# isa_cvx.net
KiCad netlist of a schematic drawn in EAGLE
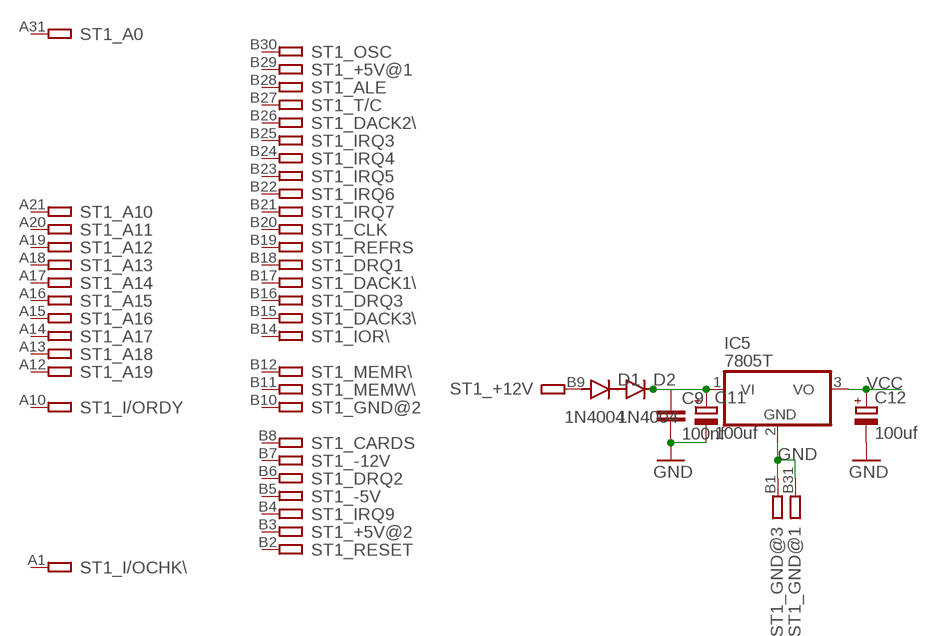
[diagram p0: schematic, sheet 1, part 1 of 2]
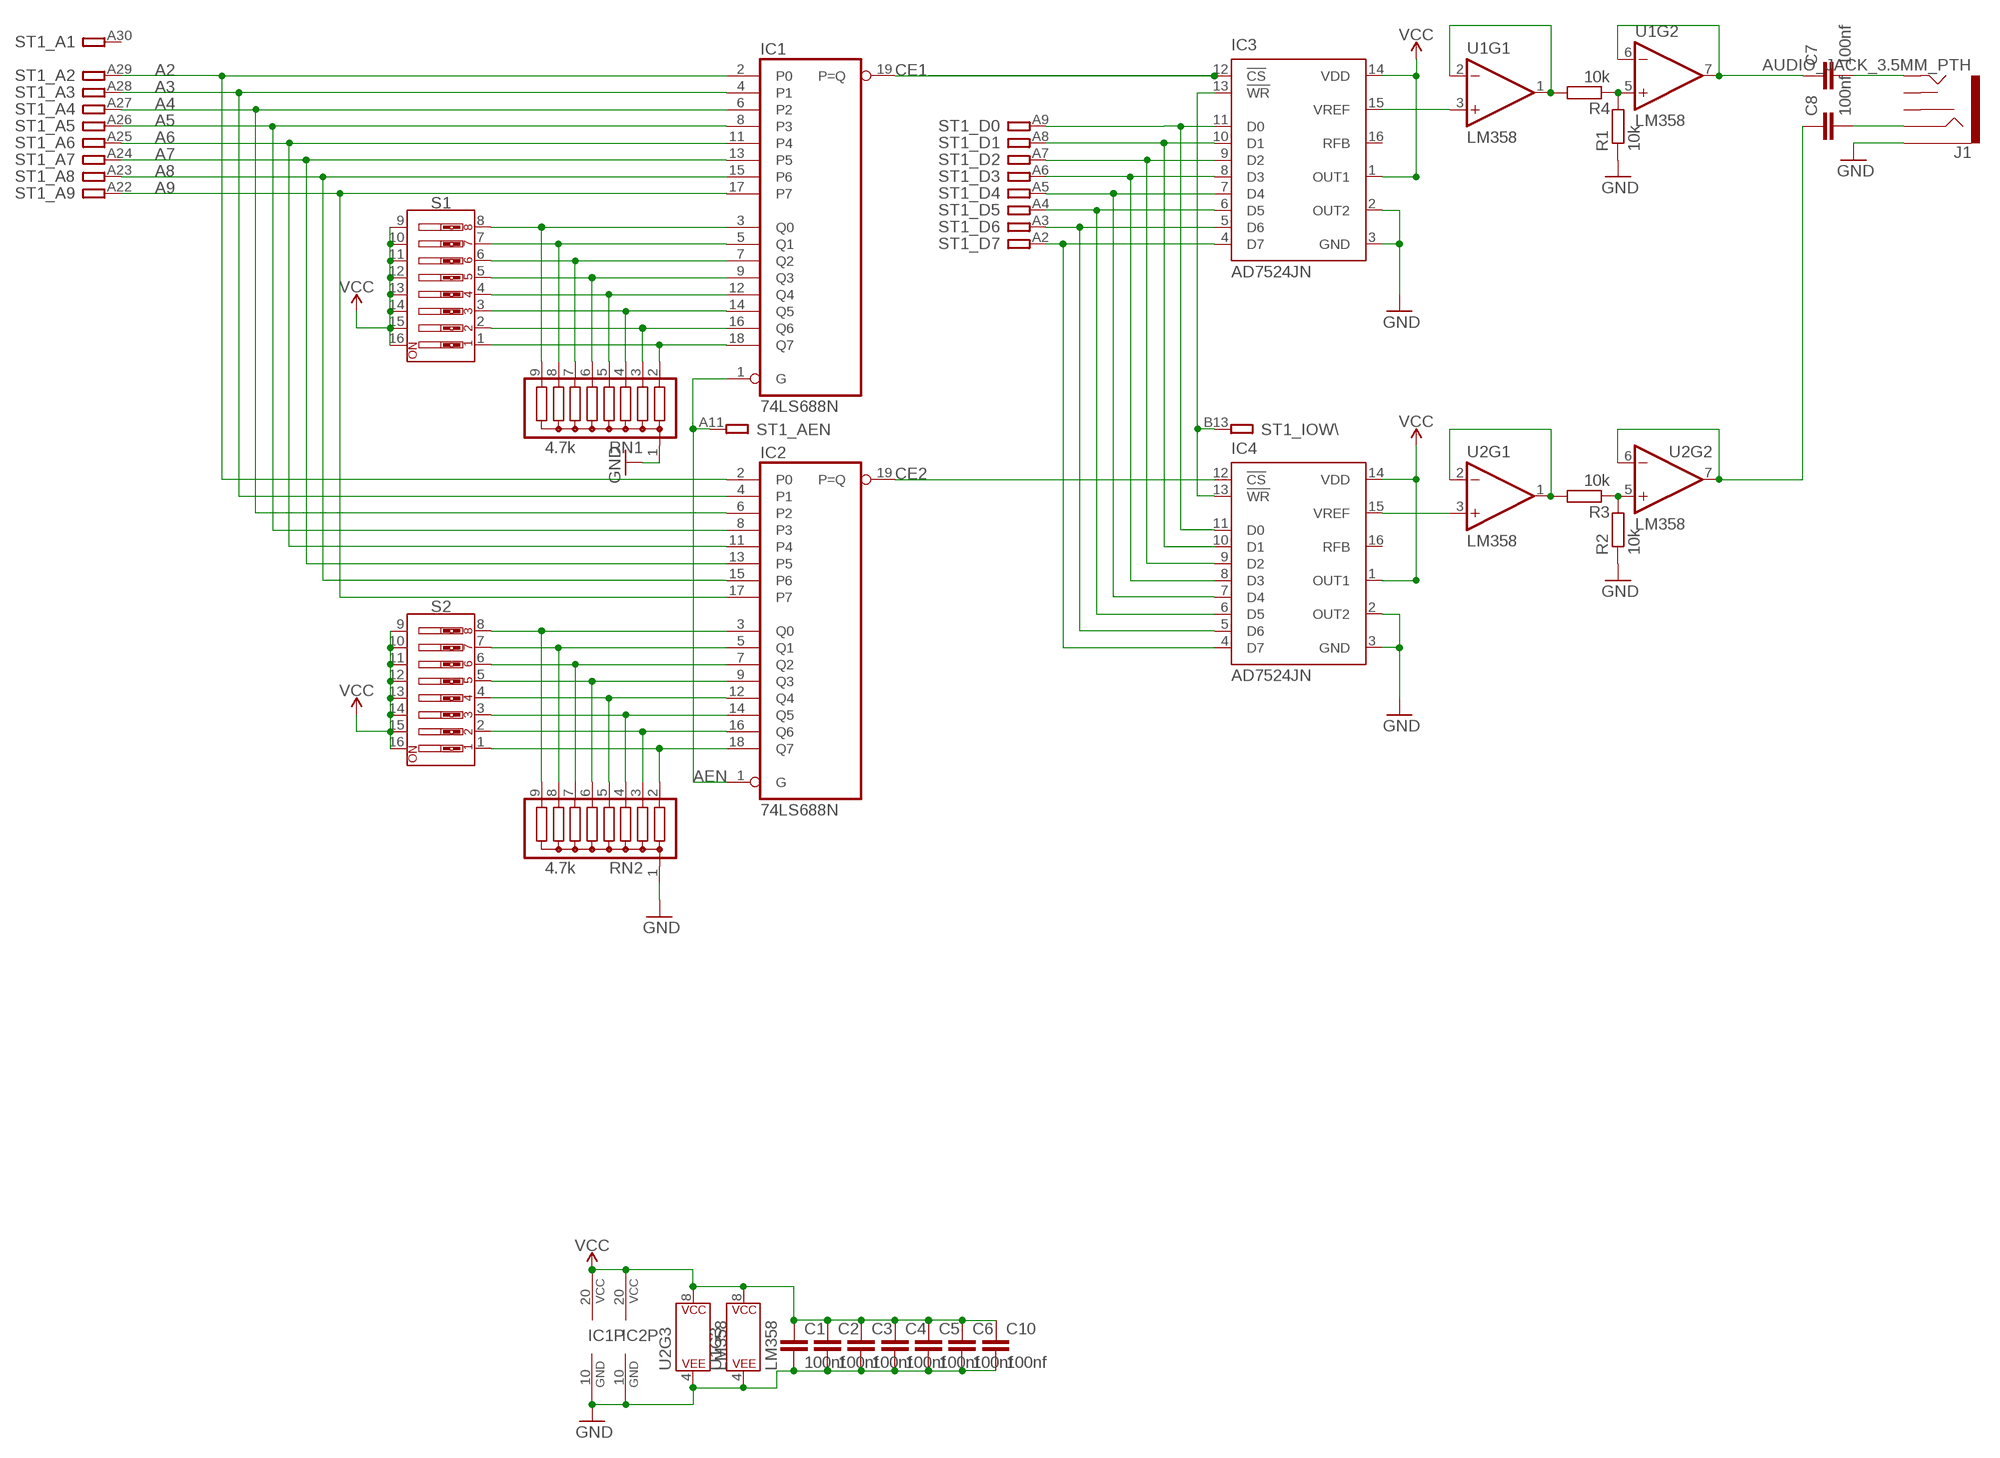
[diagram p1: schematic, sheet 1, part 2 of 2]

(export (version "E")
  (design (tool "Eeschema 10.0.6"))
  (components
    (comp (ref "C1")
      (value "100nf")
      (footprint "eagle-import:C2.5-2")
      (libsource (lib "eagle-import") (part "C2.5/2"))
    )
    (comp (ref "C2")
      (value "100nf")
      (footprint "eagle-import:C2.5-2")
      (libsource (lib "eagle-import") (part "C2.5/2"))
    )
    (comp (ref "C3")
      (value "100nf")
      (footprint "eagle-import:C2.5-2")
      (libsource (lib "eagle-import") (part "C2.5/2"))
    )
    (comp (ref "C4")
      (value "100nf")
      (footprint "eagle-import:C2.5-2")
      (libsource (lib "eagle-import") (part "C2.5/2"))
    )
    (comp (ref "C5")
      (value "100nf")
      (footprint "eagle-import:C2.5-2")
      (libsource (lib "eagle-import") (part "C2.5/2"))
    )
    (comp (ref "C6")
      (value "100nf")
      (footprint "eagle-import:C2.5-2")
      (libsource (lib "eagle-import") (part "C2.5/2"))
    )
    (comp (ref "C7")
      (value "100nf")
      (footprint "eagle-import:C2.5-2")
      (libsource (lib "eagle-import") (part "C2.5/2"))
    )
    (comp (ref "C8")
      (value "100nf")
      (footprint "eagle-import:C2.5-2")
      (libsource (lib "eagle-import") (part "C2.5/2"))
    )
    (comp (ref "C9")
      (value "100nf")
      (footprint "eagle-import:C2.5-2")
      (libsource (lib "eagle-import") (part "C2.5/2"))
    )
    (comp (ref "C10")
      (value "100nf")
      (footprint "eagle-import:C2.5-2")
      (libsource (lib "eagle-import") (part "C2.5/2"))
    )
    (comp (ref "C11")
      (value "100uf")
      (footprint "eagle-import:E2,5-5")
      (libsource (lib "eagle-import") (part "CPOL-EUE2.5-5"))
    )
    (comp (ref "C12")
      (value "100uf")
      (footprint "eagle-import:E2,5-5")
      (libsource (lib "eagle-import") (part "CPOL-EUE2.5-5"))
    )
    (comp (ref "D1")
      (value "1N4004")
      (footprint "eagle-import:DO41-10")
      (libsource (lib "eagle-import") (part "1N4004"))
    )
    (comp (ref "D2")
      (value "1N4004")
      (footprint "eagle-import:DO41-10")
      (libsource (lib "eagle-import") (part "1N4004"))
    )
    (comp (ref "IC1")
      (value "74LS688N")
      (footprint "eagle-import:DIL20")
      (libsource (lib "eagle-import") (part "74688NLS"))
    )
    (comp (ref "IC2")
      (value "74LS688N")
      (footprint "eagle-import:DIL20")
      (libsource (lib "eagle-import") (part "74688NLS"))
    )
    (comp (ref "IC3")
      (value "AD7524JN")
      (footprint "eagle-import:DIL16")
      (fields (field (name "MF") "ALTERA CORPORATION") (field (name "MPN") "AD7524JNZ"))
      (libsource (lib "eagle-import") (part "AD7524NJ"))
    )
    (comp (ref "IC4")
      (value "AD7524JN")
      (footprint "eagle-import:DIL16")
      (fields (field (name "MF") "ALTERA CORPORATION") (field (name "MPN") "AD7524JNZ"))
      (libsource (lib "eagle-import") (part "AD7524NJ"))
    )
    (comp (ref "IC5")
      (value "7805T")
      (footprint "eagle-import:TO220H")
      (libsource (lib "eagle-import") (part "78T05"))
    )
    (comp (ref "J1")
      (value "AUDIO_JACK_3.5MM_PTH")
      (footprint "eagle-import:AUDIO-JACK")
      (libsource (lib "eagle-import") (part "AUDIO_JACK_3.5MM_PTH"))
    )
    (comp (ref "R1")
      (value "10k")
      (footprint "eagle-import:0207_10")
      (libsource (lib "eagle-import") (part "R-EU_0207/10"))
    )
    (comp (ref "R2")
      (value "10k")
      (footprint "eagle-import:0207_10")
      (libsource (lib "eagle-import") (part "R-EU_0207/10"))
    )
    (comp (ref "R3")
      (value "10k")
      (footprint "eagle-import:0207_10")
      (libsource (lib "eagle-import") (part "R-EU_0207/10"))
    )
    (comp (ref "R4")
      (value "10k")
      (footprint "eagle-import:0207_10")
      (libsource (lib "eagle-import") (part "R-EU_0207/10"))
    )
    (comp (ref "RN1")
      (value "4.7k")
      (footprint "eagle-import:SIL9")
      (libsource (lib "eagle-import") (part "G08R"))
    )
    (comp (ref "RN2")
      (value "4.7k")
      (footprint "eagle-import:SIL9")
      (libsource (lib "eagle-import") (part "G08R"))
    )
    (comp (ref "S1")
      (value "DIP-08-PTH")
      (footprint "eagle-import:DIPSWITCH-08")
      (libsource (lib "eagle-import") (part "DIP-08-PTH"))
    )
    (comp (ref "S2")
      (value "DIP-08-PTH")
      (footprint "eagle-import:DIPSWITCH-08")
      (libsource (lib "eagle-import") (part "DIP-08-PTH"))
    )
    (comp (ref "ST1")
      (value "IBM8BIT")
      (footprint "eagle-import:IBM8BIT")
      (libsource (lib "eagle-import") (part "IBM8BIT"))
    )
    (comp (ref "U1")
      (value "LM358")
      (footprint "eagle-import:DIP08")
      (libsource (lib "eagle-import") (part "LM358"))
    )
    (comp (ref "U2")
      (value "LM358")
      (footprint "eagle-import:DIP08")
      (libsource (lib "eagle-import") (part "LM358"))
    )
  )
  (nets
    (net (code "1") (name "/A2") (class "Default")
      (node (ref "IC1") (pin "2") (pinfunction "P0_2") (pintype "input"))
      (node (ref "IC2") (pin "2") (pinfunction "P0_2") (pintype "input"))
      (node (ref "ST1") (pin "A29") (pinfunction "P_A29") (pintype "bidirectional"))
    )
    (net (code "2") (name "/A3") (class "Default")
      (node (ref "IC1") (pin "4") (pinfunction "P1_4") (pintype "input"))
      (node (ref "IC2") (pin "4") (pinfunction "P1_4") (pintype "input"))
      (node (ref "ST1") (pin "A28") (pinfunction "P_A28") (pintype "bidirectional"))
    )
    (net (code "3") (name "/A4") (class "Default")
      (node (ref "IC1") (pin "6") (pinfunction "P2_6") (pintype "input"))
      (node (ref "IC2") (pin "6") (pinfunction "P2_6") (pintype "input"))
      (node (ref "ST1") (pin "A27") (pinfunction "P_A27") (pintype "bidirectional"))
    )
    (net (code "4") (name "/A5") (class "Default")
      (node (ref "IC1") (pin "8") (pinfunction "P3_8") (pintype "input"))
      (node (ref "IC2") (pin "8") (pinfunction "P3_8") (pintype "input"))
      (node (ref "ST1") (pin "A26") (pinfunction "P_A26") (pintype "bidirectional"))
    )
    (net (code "5") (name "/A6") (class "Default")
      (node (ref "IC1") (pin "11") (pinfunction "P4_11") (pintype "input"))
      (node (ref "IC2") (pin "11") (pinfunction "P4_11") (pintype "input"))
      (node (ref "ST1") (pin "A25") (pinfunction "P_A25") (pintype "bidirectional"))
    )
    (net (code "6") (name "/A7") (class "Default")
      (node (ref "IC1") (pin "13") (pinfunction "P5_13") (pintype "input"))
      (node (ref "IC2") (pin "13") (pinfunction "P5_13") (pintype "input"))
      (node (ref "ST1") (pin "A24") (pinfunction "P_A24") (pintype "bidirectional"))
    )
    (net (code "7") (name "/A8") (class "Default")
      (node (ref "IC1") (pin "15") (pinfunction "P6_15") (pintype "input"))
      (node (ref "IC2") (pin "15") (pinfunction "P6_15") (pintype "input"))
      (node (ref "ST1") (pin "A23") (pinfunction "P_A23") (pintype "bidirectional"))
    )
    (net (code "8") (name "/A9") (class "Default")
      (node (ref "IC1") (pin "17") (pinfunction "P7_17") (pintype "input"))
      (node (ref "IC2") (pin "17") (pinfunction "P7_17") (pintype "input"))
      (node (ref "ST1") (pin "A22") (pinfunction "P_A22") (pintype "bidirectional"))
    )
    (net (code "9") (name "/AEN") (class "Default")
      (node (ref "IC1") (pin "1") (pinfunction "G_1") (pintype "input"))
      (node (ref "IC2") (pin "1") (pinfunction "G_1") (pintype "input"))
      (node (ref "ST1") (pin "A11") (pinfunction "P_A11") (pintype "bidirectional"))
    )
    (net (code "10") (name "/CE1") (class "Default")
      (node (ref "IC1") (pin "19") (pinfunction "P=Q_19") (pintype "output"))
      (node (ref "IC3") (pin "12") (pinfunction "~{CS}_12") (pintype "input"))
    )
    (net (code "11") (name "/CE2") (class "Default")
      (node (ref "IC2") (pin "19") (pinfunction "P=Q_19") (pintype "output"))
      (node (ref "IC4") (pin "12") (pinfunction "~{CS}_12") (pintype "input"))
    )
    (net (code "12") (name "GND") (class "Default")
      (node (ref "C1") (pin "2") (pinfunction "2_2") (pintype "passive"))
      (node (ref "C10") (pin "2") (pinfunction "2_2") (pintype "passive"))
      (node (ref "C11") (pin "-") (pinfunction "-_-") (pintype "passive"))
      (node (ref "C12") (pin "-") (pinfunction "-_-") (pintype "passive"))
      (node (ref "C2") (pin "2") (pinfunction "2_2") (pintype "passive"))
      (node (ref "C3") (pin "2") (pinfunction "2_2") (pintype "passive"))
      (node (ref "C4") (pin "2") (pinfunction "2_2") (pintype "passive"))
      (node (ref "C5") (pin "2") (pinfunction "2_2") (pintype "passive"))
      (node (ref "C6") (pin "2") (pinfunction "2_2") (pintype "passive"))
      (node (ref "C9") (pin "2") (pinfunction "2_2") (pintype "passive"))
      (node (ref "IC1") (pin "10") (pinfunction "GND_10") (pintype "power_in"))
      (node (ref "IC2") (pin "10") (pinfunction "GND_10") (pintype "power_in"))
      (node (ref "IC3") (pin "2") (pinfunction "OUT2_2") (pintype "passive"))
      (node (ref "IC3") (pin "3") (pinfunction "GND_3") (pintype "power_in"))
      (node (ref "IC4") (pin "2") (pinfunction "OUT2_2") (pintype "passive"))
      (node (ref "IC4") (pin "3") (pinfunction "GND_3") (pintype "power_in"))
      (node (ref "IC5") (pin "2") (pinfunction "GND_2") (pintype "passive"))
      (node (ref "J1") (pin "SLEEVE") (pinfunction "SLEEVE_SLEEVE") (pintype "bidirectional"))
      (node (ref "R1") (pin "1") (pinfunction "1_1") (pintype "passive"))
      (node (ref "R2") (pin "1") (pinfunction "1_1") (pintype "passive"))
      (node (ref "RN1") (pin "1") (pinfunction "1_1") (pintype "passive"))
      (node (ref "RN2") (pin "1") (pinfunction "1_1") (pintype "passive"))
      (node (ref "ST1") (pin "B1") (pinfunction "P_B1") (pintype "bidirectional"))
      (node (ref "ST1") (pin "B31") (pinfunction "P_B31") (pintype "bidirectional"))
      (node (ref "U1") (pin "4") (pinfunction "P$V-_4") (pintype "bidirectional"))
      (node (ref "U2") (pin "4") (pinfunction "P$V-_4") (pintype "bidirectional"))
    )
    (net (code "13") (name "Net-(C7-Pad2)") (class "Default")
      (node (ref "C7") (pin "2") (pinfunction "2_2") (pintype "passive"))
      (node (ref "J1") (pin "TIP") (pinfunction "TIP_TIP") (pintype "bidirectional"))
    )
    (net (code "14") (name "Net-(C8-Pad2)") (class "Default")
      (node (ref "C8") (pin "2") (pinfunction "2_2") (pintype "passive"))
      (node (ref "J1") (pin "RING") (pinfunction "RING_RING") (pintype "bidirectional"))
    )
    (net (code "15") (name "Net-(D1-PadC)") (class "Default")
      (node (ref "D1") (pin "C") (pinfunction "C_C") (pintype "passive"))
      (node (ref "D2") (pin "A") (pinfunction "A_A") (pintype "passive"))
    )
    (net (code "16") (name "Net-(IC1A-Q0)") (class "Default")
      (node (ref "IC1") (pin "3") (pinfunction "Q0_3") (pintype "input"))
      (node (ref "RN1") (pin "9") (pinfunction "9_9") (pintype "passive"))
      (node (ref "S1") (pin "8") (pinfunction "8_8") (pintype "passive"))
    )
    (net (code "17") (name "Net-(IC1A-Q1)") (class "Default")
      (node (ref "IC1") (pin "5") (pinfunction "Q1_5") (pintype "input"))
      (node (ref "RN1") (pin "8") (pinfunction "8_8") (pintype "passive"))
      (node (ref "S1") (pin "7") (pinfunction "7_7") (pintype "passive"))
    )
    (net (code "18") (name "Net-(IC1A-Q2)") (class "Default")
      (node (ref "IC1") (pin "7") (pinfunction "Q2_7") (pintype "input"))
      (node (ref "RN1") (pin "7") (pinfunction "7_7") (pintype "passive"))
      (node (ref "S1") (pin "6") (pinfunction "6_6") (pintype "passive"))
    )
    (net (code "19") (name "Net-(IC1A-Q3)") (class "Default")
      (node (ref "IC1") (pin "9") (pinfunction "Q3_9") (pintype "input"))
      (node (ref "RN1") (pin "6") (pinfunction "6_6") (pintype "passive"))
      (node (ref "S1") (pin "5") (pinfunction "5_5") (pintype "passive"))
    )
    (net (code "20") (name "Net-(IC1A-Q4)") (class "Default")
      (node (ref "IC1") (pin "12") (pinfunction "Q4_12") (pintype "input"))
      (node (ref "RN1") (pin "5") (pinfunction "5_5") (pintype "passive"))
      (node (ref "S1") (pin "4") (pinfunction "4_4") (pintype "passive"))
    )
    (net (code "21") (name "Net-(IC1A-Q5)") (class "Default")
      (node (ref "IC1") (pin "14") (pinfunction "Q5_14") (pintype "input"))
      (node (ref "RN1") (pin "4") (pinfunction "4_4") (pintype "passive"))
      (node (ref "S1") (pin "3") (pinfunction "3_3") (pintype "passive"))
    )
    (net (code "22") (name "Net-(IC1A-Q6)") (class "Default")
      (node (ref "IC1") (pin "16") (pinfunction "Q6_16") (pintype "input"))
      (node (ref "RN1") (pin "3") (pinfunction "3_3") (pintype "passive"))
      (node (ref "S1") (pin "2") (pinfunction "2_2") (pintype "passive"))
    )
    (net (code "23") (name "Net-(IC1A-Q7)") (class "Default")
      (node (ref "IC1") (pin "18") (pinfunction "Q7_18") (pintype "input"))
      (node (ref "RN1") (pin "2") (pinfunction "2_2") (pintype "passive"))
      (node (ref "S1") (pin "1") (pinfunction "1_1") (pintype "passive"))
    )
    (net (code "24") (name "Net-(IC2A-Q0)") (class "Default")
      (node (ref "IC2") (pin "3") (pinfunction "Q0_3") (pintype "input"))
      (node (ref "RN2") (pin "9") (pinfunction "9_9") (pintype "passive"))
      (node (ref "S2") (pin "8") (pinfunction "8_8") (pintype "passive"))
    )
    (net (code "25") (name "Net-(IC2A-Q1)") (class "Default")
      (node (ref "IC2") (pin "5") (pinfunction "Q1_5") (pintype "input"))
      (node (ref "RN2") (pin "8") (pinfunction "8_8") (pintype "passive"))
      (node (ref "S2") (pin "7") (pinfunction "7_7") (pintype "passive"))
    )
    (net (code "26") (name "Net-(IC2A-Q2)") (class "Default")
      (node (ref "IC2") (pin "7") (pinfunction "Q2_7") (pintype "input"))
      (node (ref "RN2") (pin "7") (pinfunction "7_7") (pintype "passive"))
      (node (ref "S2") (pin "6") (pinfunction "6_6") (pintype "passive"))
    )
    (net (code "27") (name "Net-(IC2A-Q3)") (class "Default")
      (node (ref "IC2") (pin "9") (pinfunction "Q3_9") (pintype "input"))
      (node (ref "RN2") (pin "6") (pinfunction "6_6") (pintype "passive"))
      (node (ref "S2") (pin "5") (pinfunction "5_5") (pintype "passive"))
    )
    (net (code "28") (name "Net-(IC2A-Q4)") (class "Default")
      (node (ref "IC2") (pin "12") (pinfunction "Q4_12") (pintype "input"))
      (node (ref "RN2") (pin "5") (pinfunction "5_5") (pintype "passive"))
      (node (ref "S2") (pin "4") (pinfunction "4_4") (pintype "passive"))
    )
    (net (code "29") (name "Net-(IC2A-Q5)") (class "Default")
      (node (ref "IC2") (pin "14") (pinfunction "Q5_14") (pintype "input"))
      (node (ref "RN2") (pin "4") (pinfunction "4_4") (pintype "passive"))
      (node (ref "S2") (pin "3") (pinfunction "3_3") (pintype "passive"))
    )
    (net (code "30") (name "Net-(IC2A-Q6)") (class "Default")
      (node (ref "IC2") (pin "16") (pinfunction "Q6_16") (pintype "input"))
      (node (ref "RN2") (pin "3") (pinfunction "3_3") (pintype "passive"))
      (node (ref "S2") (pin "2") (pinfunction "2_2") (pintype "passive"))
    )
    (net (code "31") (name "Net-(IC2A-Q7)") (class "Default")
      (node (ref "IC2") (pin "18") (pinfunction "Q7_18") (pintype "input"))
      (node (ref "RN2") (pin "2") (pinfunction "2_2") (pintype "passive"))
      (node (ref "S2") (pin "1") (pinfunction "1_1") (pintype "passive"))
    )
    (net (code "32") (name "Net-(IC3-D0)") (class "Default")
      (node (ref "IC3") (pin "11") (pinfunction "D0_11") (pintype "input"))
      (node (ref "IC4") (pin "11") (pinfunction "D0_11") (pintype "input"))
      (node (ref "ST1") (pin "A9") (pinfunction "P_A9") (pintype "bidirectional"))
    )
    (net (code "33") (name "Net-(IC3-D1)") (class "Default")
      (node (ref "IC3") (pin "10") (pinfunction "D1_10") (pintype "input"))
      (node (ref "IC4") (pin "10") (pinfunction "D1_10") (pintype "input"))
      (node (ref "ST1") (pin "A8") (pinfunction "P_A8") (pintype "bidirectional"))
    )
    (net (code "34") (name "Net-(IC3-D2)") (class "Default")
      (node (ref "IC3") (pin "9") (pinfunction "D2_9") (pintype "input"))
      (node (ref "IC4") (pin "9") (pinfunction "D2_9") (pintype "input"))
      (node (ref "ST1") (pin "A7") (pinfunction "P_A7") (pintype "bidirectional"))
    )
    (net (code "35") (name "Net-(IC3-D3)") (class "Default")
      (node (ref "IC3") (pin "8") (pinfunction "D3_8") (pintype "input"))
      (node (ref "IC4") (pin "8") (pinfunction "D3_8") (pintype "input"))
      (node (ref "ST1") (pin "A6") (pinfunction "P_A6") (pintype "bidirectional"))
    )
    (net (code "36") (name "Net-(IC3-D4)") (class "Default")
      (node (ref "IC3") (pin "7") (pinfunction "D4_7") (pintype "input"))
      (node (ref "IC4") (pin "7") (pinfunction "D4_7") (pintype "input"))
      (node (ref "ST1") (pin "A5") (pinfunction "P_A5") (pintype "bidirectional"))
    )
    (net (code "37") (name "Net-(IC3-D5)") (class "Default")
      (node (ref "IC3") (pin "6") (pinfunction "D5_6") (pintype "input"))
      (node (ref "IC4") (pin "6") (pinfunction "D5_6") (pintype "input"))
      (node (ref "ST1") (pin "A4") (pinfunction "P_A4") (pintype "bidirectional"))
    )
    (net (code "38") (name "Net-(IC3-D6)") (class "Default")
      (node (ref "IC3") (pin "5") (pinfunction "D6_5") (pintype "input"))
      (node (ref "IC4") (pin "5") (pinfunction "D6_5") (pintype "input"))
      (node (ref "ST1") (pin "A3") (pinfunction "P_A3") (pintype "bidirectional"))
    )
    (net (code "39") (name "Net-(IC3-D7)") (class "Default")
      (node (ref "IC3") (pin "4") (pinfunction "D7_4") (pintype "input"))
      (node (ref "IC4") (pin "4") (pinfunction "D7_4") (pintype "input"))
      (node (ref "ST1") (pin "A2") (pinfunction "P_A2") (pintype "bidirectional"))
    )
    (net (code "40") (name "Net-(IC3-VREF)") (class "Default")
      (node (ref "IC3") (pin "15") (pinfunction "VREF_15") (pintype "input"))
      (node (ref "U1") (pin "3") (pinfunction "+IN_3") (pintype "input"))
    )
    (net (code "41") (name "Net-(IC3-~{WR})") (class "Default")
      (node (ref "IC3") (pin "13") (pinfunction "~{WR}_13") (pintype "input"))
      (node (ref "IC4") (pin "13") (pinfunction "~{WR}_13") (pintype "input"))
      (node (ref "ST1") (pin "B13") (pinfunction "P_B13") (pintype "bidirectional"))
    )
    (net (code "42") (name "Net-(IC4-VREF)") (class "Default")
      (node (ref "IC4") (pin "15") (pinfunction "VREF_15") (pintype "input"))
      (node (ref "U2") (pin "3") (pinfunction "+IN_3") (pintype "input"))
    )
    (net (code "43") (name "Net-(IC5-VI)") (class "Default")
      (node (ref "C11") (pin "+") (pinfunction "+_+") (pintype "passive"))
      (node (ref "C9") (pin "1") (pinfunction "1_1") (pintype "passive"))
      (node (ref "D2") (pin "C") (pinfunction "C_C") (pintype "passive"))
      (node (ref "IC5") (pin "1") (pinfunction "VI_1") (pintype "input"))
    )
    (net (code "44") (name "Net-(ST1A-P)") (class "Default")
      (node (ref "D1") (pin "A") (pinfunction "A_A") (pintype "passive"))
      (node (ref "ST1") (pin "B9") (pinfunction "P_B9") (pintype "bidirectional"))
    )
    (net (code "45") (name "Net-(U1A--IN)") (class "Default")
      (node (ref "R4") (pin "2") (pinfunction "2_2") (pintype "passive"))
      (node (ref "U1") (pin "1") (pinfunction "OUT_1") (pintype "output"))
      (node (ref "U1") (pin "2") (pinfunction "-IN_2") (pintype "input"))
    )
    (net (code "46") (name "Net-(U1B-+IN)") (class "Default")
      (node (ref "R1") (pin "2") (pinfunction "2_2") (pintype "passive"))
      (node (ref "R4") (pin "1") (pinfunction "1_1") (pintype "passive"))
      (node (ref "U1") (pin "5") (pinfunction "+IN_5") (pintype "input"))
    )
    (net (code "47") (name "Net-(U1B--IN)") (class "Default")
      (node (ref "C7") (pin "1") (pinfunction "1_1") (pintype "passive"))
      (node (ref "U1") (pin "6") (pinfunction "-IN_6") (pintype "input"))
      (node (ref "U1") (pin "7") (pinfunction "OUT_7") (pintype "output"))
    )
    (net (code "48") (name "Net-(U2A--IN)") (class "Default")
      (node (ref "R3") (pin "2") (pinfunction "2_2") (pintype "passive"))
      (node (ref "U2") (pin "1") (pinfunction "OUT_1") (pintype "output"))
      (node (ref "U2") (pin "2") (pinfunction "-IN_2") (pintype "input"))
    )
    (net (code "49") (name "Net-(U2B-+IN)") (class "Default")
      (node (ref "R2") (pin "2") (pinfunction "2_2") (pintype "passive"))
      (node (ref "R3") (pin "1") (pinfunction "1_1") (pintype "passive"))
      (node (ref "U2") (pin "5") (pinfunction "+IN_5") (pintype "input"))
    )
    (net (code "50") (name "Net-(U2B--IN)") (class "Default")
      (node (ref "C8") (pin "1") (pinfunction "1_1") (pintype "passive"))
      (node (ref "U2") (pin "6") (pinfunction "-IN_6") (pintype "input"))
      (node (ref "U2") (pin "7") (pinfunction "OUT_7") (pintype "output"))
    )
    (net (code "51") (name "VCC") (class "Default")
      (node (ref "C1") (pin "1") (pinfunction "1_1") (pintype "passive"))
      (node (ref "C10") (pin "1") (pinfunction "1_1") (pintype "passive"))
      (node (ref "C12") (pin "+") (pinfunction "+_+") (pintype "passive"))
      (node (ref "C2") (pin "1") (pinfunction "1_1") (pintype "passive"))
      (node (ref "C3") (pin "1") (pinfunction "1_1") (pintype "passive"))
      (node (ref "C4") (pin "1") (pinfunction "1_1") (pintype "passive"))
      (node (ref "C5") (pin "1") (pinfunction "1_1") (pintype "passive"))
      (node (ref "C6") (pin "1") (pinfunction "1_1") (pintype "passive"))
      (node (ref "IC1") (pin "20") (pinfunction "VCC_20") (pintype "power_in"))
      (node (ref "IC2") (pin "20") (pinfunction "VCC_20") (pintype "power_in"))
      (node (ref "IC3") (pin "1") (pinfunction "OUT1_1") (pintype "passive"))
      (node (ref "IC3") (pin "14") (pinfunction "VDD_14") (pintype "power_in"))
      (node (ref "IC4") (pin "1") (pinfunction "OUT1_1") (pintype "passive"))
      (node (ref "IC4") (pin "14") (pinfunction "VDD_14") (pintype "power_in"))
      (node (ref "IC5") (pin "3") (pinfunction "VO_3") (pintype "passive"))
      (node (ref "S1") (pin "10") (pinfunction "10_10") (pintype "passive"))
      (node (ref "S1") (pin "11") (pinfunction "11_11") (pintype "passive"))
      (node (ref "S1") (pin "12") (pinfunction "12_12") (pintype "passive"))
      (node (ref "S1") (pin "13") (pinfunction "13_13") (pintype "passive"))
      (node (ref "S1") (pin "14") (pinfunction "14_14") (pintype "passive"))
      (node (ref "S1") (pin "15") (pinfunction "15_15") (pintype "passive"))
      (node (ref "S1") (pin "16") (pinfunction "16_16") (pintype "passive"))
      (node (ref "S1") (pin "9") (pinfunction "9_9") (pintype "passive"))
      (node (ref "S2") (pin "10") (pinfunction "10_10") (pintype "passive"))
      (node (ref "S2") (pin "11") (pinfunction "11_11") (pintype "passive"))
      (node (ref "S2") (pin "12") (pinfunction "12_12") (pintype "passive"))
      (node (ref "S2") (pin "13") (pinfunction "13_13") (pintype "passive"))
      (node (ref "S2") (pin "14") (pinfunction "14_14") (pintype "passive"))
      (node (ref "S2") (pin "15") (pinfunction "15_15") (pintype "passive"))
      (node (ref "S2") (pin "16") (pinfunction "16_16") (pintype "passive"))
      (node (ref "S2") (pin "9") (pinfunction "9_9") (pintype "passive"))
      (node (ref "U1") (pin "8") (pinfunction "P$V+_8") (pintype "bidirectional"))
      (node (ref "U2") (pin "8") (pinfunction "P$V+_8") (pintype "bidirectional"))
    )
    (net (code "52") (name "unconnected-(IC3-RFB-Pad16)") (class "Default")
      (node (ref "IC3") (pin "16") (pinfunction "RFB_16") (pintype "passive"))
    )
    (net (code "53") (name "unconnected-(IC4-RFB-Pad16)") (class "Default")
      (node (ref "IC4") (pin "16") (pinfunction "RFB_16") (pintype "passive"))
    )
    (net (code "54") (name "unconnected-(J1-PadRSH)") (class "Default")
      (node (ref "J1") (pin "RSH") (pinfunction "RSH_RSH") (pintype "bidirectional"))
    )
    (net (code "55") (name "unconnected-(J1-PadTSH)") (class "Default")
      (node (ref "J1") (pin "TSH") (pinfunction "TSH_TSH") (pintype "bidirectional"))
    )
    (net (code "56") (name "unconnected-(ST1AA-P-PadB28)") (class "Default")
      (node (ref "ST1") (pin "B28") (pinfunction "P_B28") (pintype "bidirectional"))
    )
    (net (code "57") (name "unconnected-(ST1AB-P-PadB8)") (class "Default")
      (node (ref "ST1") (pin "B8") (pinfunction "P_B8") (pintype "bidirectional"))
    )
    (net (code "58") (name "unconnected-(ST1AC-P-PadB20)") (class "Default")
      (node (ref "ST1") (pin "B20") (pinfunction "P_B20") (pintype "bidirectional"))
    )
    (net (code "59") (name "unconnected-(ST1AL-P-PadB17)") (class "Default")
      (node (ref "ST1") (pin "B17") (pinfunction "P_B17") (pintype "bidirectional"))
    )
    (net (code "60") (name "unconnected-(ST1AM-P-PadB26)") (class "Default")
      (node (ref "ST1") (pin "B26") (pinfunction "P_B26") (pintype "bidirectional"))
    )
    (net (code "61") (name "unconnected-(ST1AN-P-PadB15)") (class "Default")
      (node (ref "ST1") (pin "B15") (pinfunction "P_B15") (pintype "bidirectional"))
    )
    (net (code "62") (name "unconnected-(ST1AO-P-PadB18)") (class "Default")
      (node (ref "ST1") (pin "B18") (pinfunction "P_B18") (pintype "bidirectional"))
    )
    (net (code "63") (name "unconnected-(ST1AP-P-PadB6)") (class "Default")
      (node (ref "ST1") (pin "B6") (pinfunction "P_B6") (pintype "bidirectional"))
    )
    (net (code "64") (name "unconnected-(ST1AQ-P-PadB16)") (class "Default")
      (node (ref "ST1") (pin "B16") (pinfunction "P_B16") (pintype "bidirectional"))
    )
    (net (code "65") (name "unconnected-(ST1AS-P-PadB10)") (class "Default")
      (node (ref "ST1") (pin "B10") (pinfunction "P_B10") (pintype "bidirectional"))
    )
    (net (code "66") (name "unconnected-(ST1AU-P-PadA1)") (class "Default")
      (node (ref "ST1") (pin "A1") (pinfunction "P_A1") (pintype "bidirectional"))
    )
    (net (code "67") (name "unconnected-(ST1AV-P-PadA10)") (class "Default")
      (node (ref "ST1") (pin "A10") (pinfunction "P_A10") (pintype "bidirectional"))
    )
    (net (code "68") (name "unconnected-(ST1AW-P-PadB14)") (class "Default")
      (node (ref "ST1") (pin "B14") (pinfunction "P_B14") (pintype "bidirectional"))
    )
    (net (code "69") (name "unconnected-(ST1AY-P-PadB25)") (class "Default")
      (node (ref "ST1") (pin "B25") (pinfunction "P_B25") (pintype "bidirectional"))
    )
    (net (code "70") (name "unconnected-(ST1AZ-P-PadB24)") (class "Default")
      (node (ref "ST1") (pin "B24") (pinfunction "P_B24") (pintype "bidirectional"))
    )
    (net (code "71") (name "unconnected-(ST1B-P-PadB29)") (class "Default")
      (node (ref "ST1") (pin "B29") (pinfunction "P_B29") (pintype "bidirectional"))
    )
    (net (code "72") (name "unconnected-(ST1BA-P-PadB23)") (class "Default")
      (node (ref "ST1") (pin "B23") (pinfunction "P_B23") (pintype "bidirectional"))
    )
    (net (code "73") (name "unconnected-(ST1BB-P-PadB22)") (class "Default")
      (node (ref "ST1") (pin "B22") (pinfunction "P_B22") (pintype "bidirectional"))
    )
    (net (code "74") (name "unconnected-(ST1BC-P-PadB21)") (class "Default")
      (node (ref "ST1") (pin "B21") (pinfunction "P_B21") (pintype "bidirectional"))
    )
    (net (code "75") (name "unconnected-(ST1BD-P-PadB4)") (class "Default")
      (node (ref "ST1") (pin "B4") (pinfunction "P_B4") (pintype "bidirectional"))
    )
    (net (code "76") (name "unconnected-(ST1BE-P-PadB12)") (class "Default")
      (node (ref "ST1") (pin "B12") (pinfunction "P_B12") (pintype "bidirectional"))
    )
    (net (code "77") (name "unconnected-(ST1BF-P-PadB11)") (class "Default")
      (node (ref "ST1") (pin "B11") (pinfunction "P_B11") (pintype "bidirectional"))
    )
    (net (code "78") (name "unconnected-(ST1BG-P-PadB30)") (class "Default")
      (node (ref "ST1") (pin "B30") (pinfunction "P_B30") (pintype "bidirectional"))
    )
    (net (code "79") (name "unconnected-(ST1BH-P-PadB19)") (class "Default")
      (node (ref "ST1") (pin "B19") (pinfunction "P_B19") (pintype "bidirectional"))
    )
    (net (code "80") (name "unconnected-(ST1BI-P-PadB2)") (class "Default")
      (node (ref "ST1") (pin "B2") (pinfunction "P_B2") (pintype "bidirectional"))
    )
    (net (code "81") (name "unconnected-(ST1BJ-P-PadB27)") (class "Default")
      (node (ref "ST1") (pin "B27") (pinfunction "P_B27") (pintype "bidirectional"))
    )
    (net (code "82") (name "unconnected-(ST1C-P-PadB3)") (class "Default")
      (node (ref "ST1") (pin "B3") (pinfunction "P_B3") (pintype "bidirectional"))
    )
    (net (code "83") (name "unconnected-(ST1D-P-PadB7)") (class "Default")
      (node (ref "ST1") (pin "B7") (pinfunction "P_B7") (pintype "bidirectional"))
    )
    (net (code "84") (name "unconnected-(ST1E-P-PadB5)") (class "Default")
      (node (ref "ST1") (pin "B5") (pinfunction "P_B5") (pintype "bidirectional"))
    )
    (net (code "85") (name "unconnected-(ST1F-P-PadA31)") (class "Default")
      (node (ref "ST1") (pin "A31") (pinfunction "P_A31") (pintype "bidirectional"))
    )
    (net (code "86") (name "unconnected-(ST1G-P-PadA30)") (class "Default")
      (node (ref "ST1") (pin "A30") (pinfunction "P_A30") (pintype "bidirectional"))
    )
    (net (code "87") (name "unconnected-(ST1H-P-PadA21)") (class "Default")
      (node (ref "ST1") (pin "A21") (pinfunction "P_A21") (pintype "bidirectional"))
    )
    (net (code "88") (name "unconnected-(ST1I-P-PadA20)") (class "Default")
      (node (ref "ST1") (pin "A20") (pinfunction "P_A20") (pintype "bidirectional"))
    )
    (net (code "89") (name "unconnected-(ST1J-P-PadA19)") (class "Default")
      (node (ref "ST1") (pin "A19") (pinfunction "P_A19") (pintype "bidirectional"))
    )
    (net (code "90") (name "unconnected-(ST1K-P-PadA18)") (class "Default")
      (node (ref "ST1") (pin "A18") (pinfunction "P_A18") (pintype "bidirectional"))
    )
    (net (code "91") (name "unconnected-(ST1L-P-PadA17)") (class "Default")
      (node (ref "ST1") (pin "A17") (pinfunction "P_A17") (pintype "bidirectional"))
    )
    (net (code "92") (name "unconnected-(ST1M-P-PadA16)") (class "Default")
      (node (ref "ST1") (pin "A16") (pinfunction "P_A16") (pintype "bidirectional"))
    )
    (net (code "93") (name "unconnected-(ST1N-P-PadA15)") (class "Default")
      (node (ref "ST1") (pin "A15") (pinfunction "P_A15") (pintype "bidirectional"))
    )
    (net (code "94") (name "unconnected-(ST1O-P-PadA14)") (class "Default")
      (node (ref "ST1") (pin "A14") (pinfunction "P_A14") (pintype "bidirectional"))
    )
    (net (code "95") (name "unconnected-(ST1P-P-PadA13)") (class "Default")
      (node (ref "ST1") (pin "A13") (pinfunction "P_A13") (pintype "bidirectional"))
    )
    (net (code "96") (name "unconnected-(ST1Q-P-PadA12)") (class "Default")
      (node (ref "ST1") (pin "A12") (pinfunction "P_A12") (pintype "bidirectional"))
    )
  )
)
